# 4_324_039__3_2.net
KiCad netlist of a schematic drawn in Altium Designer
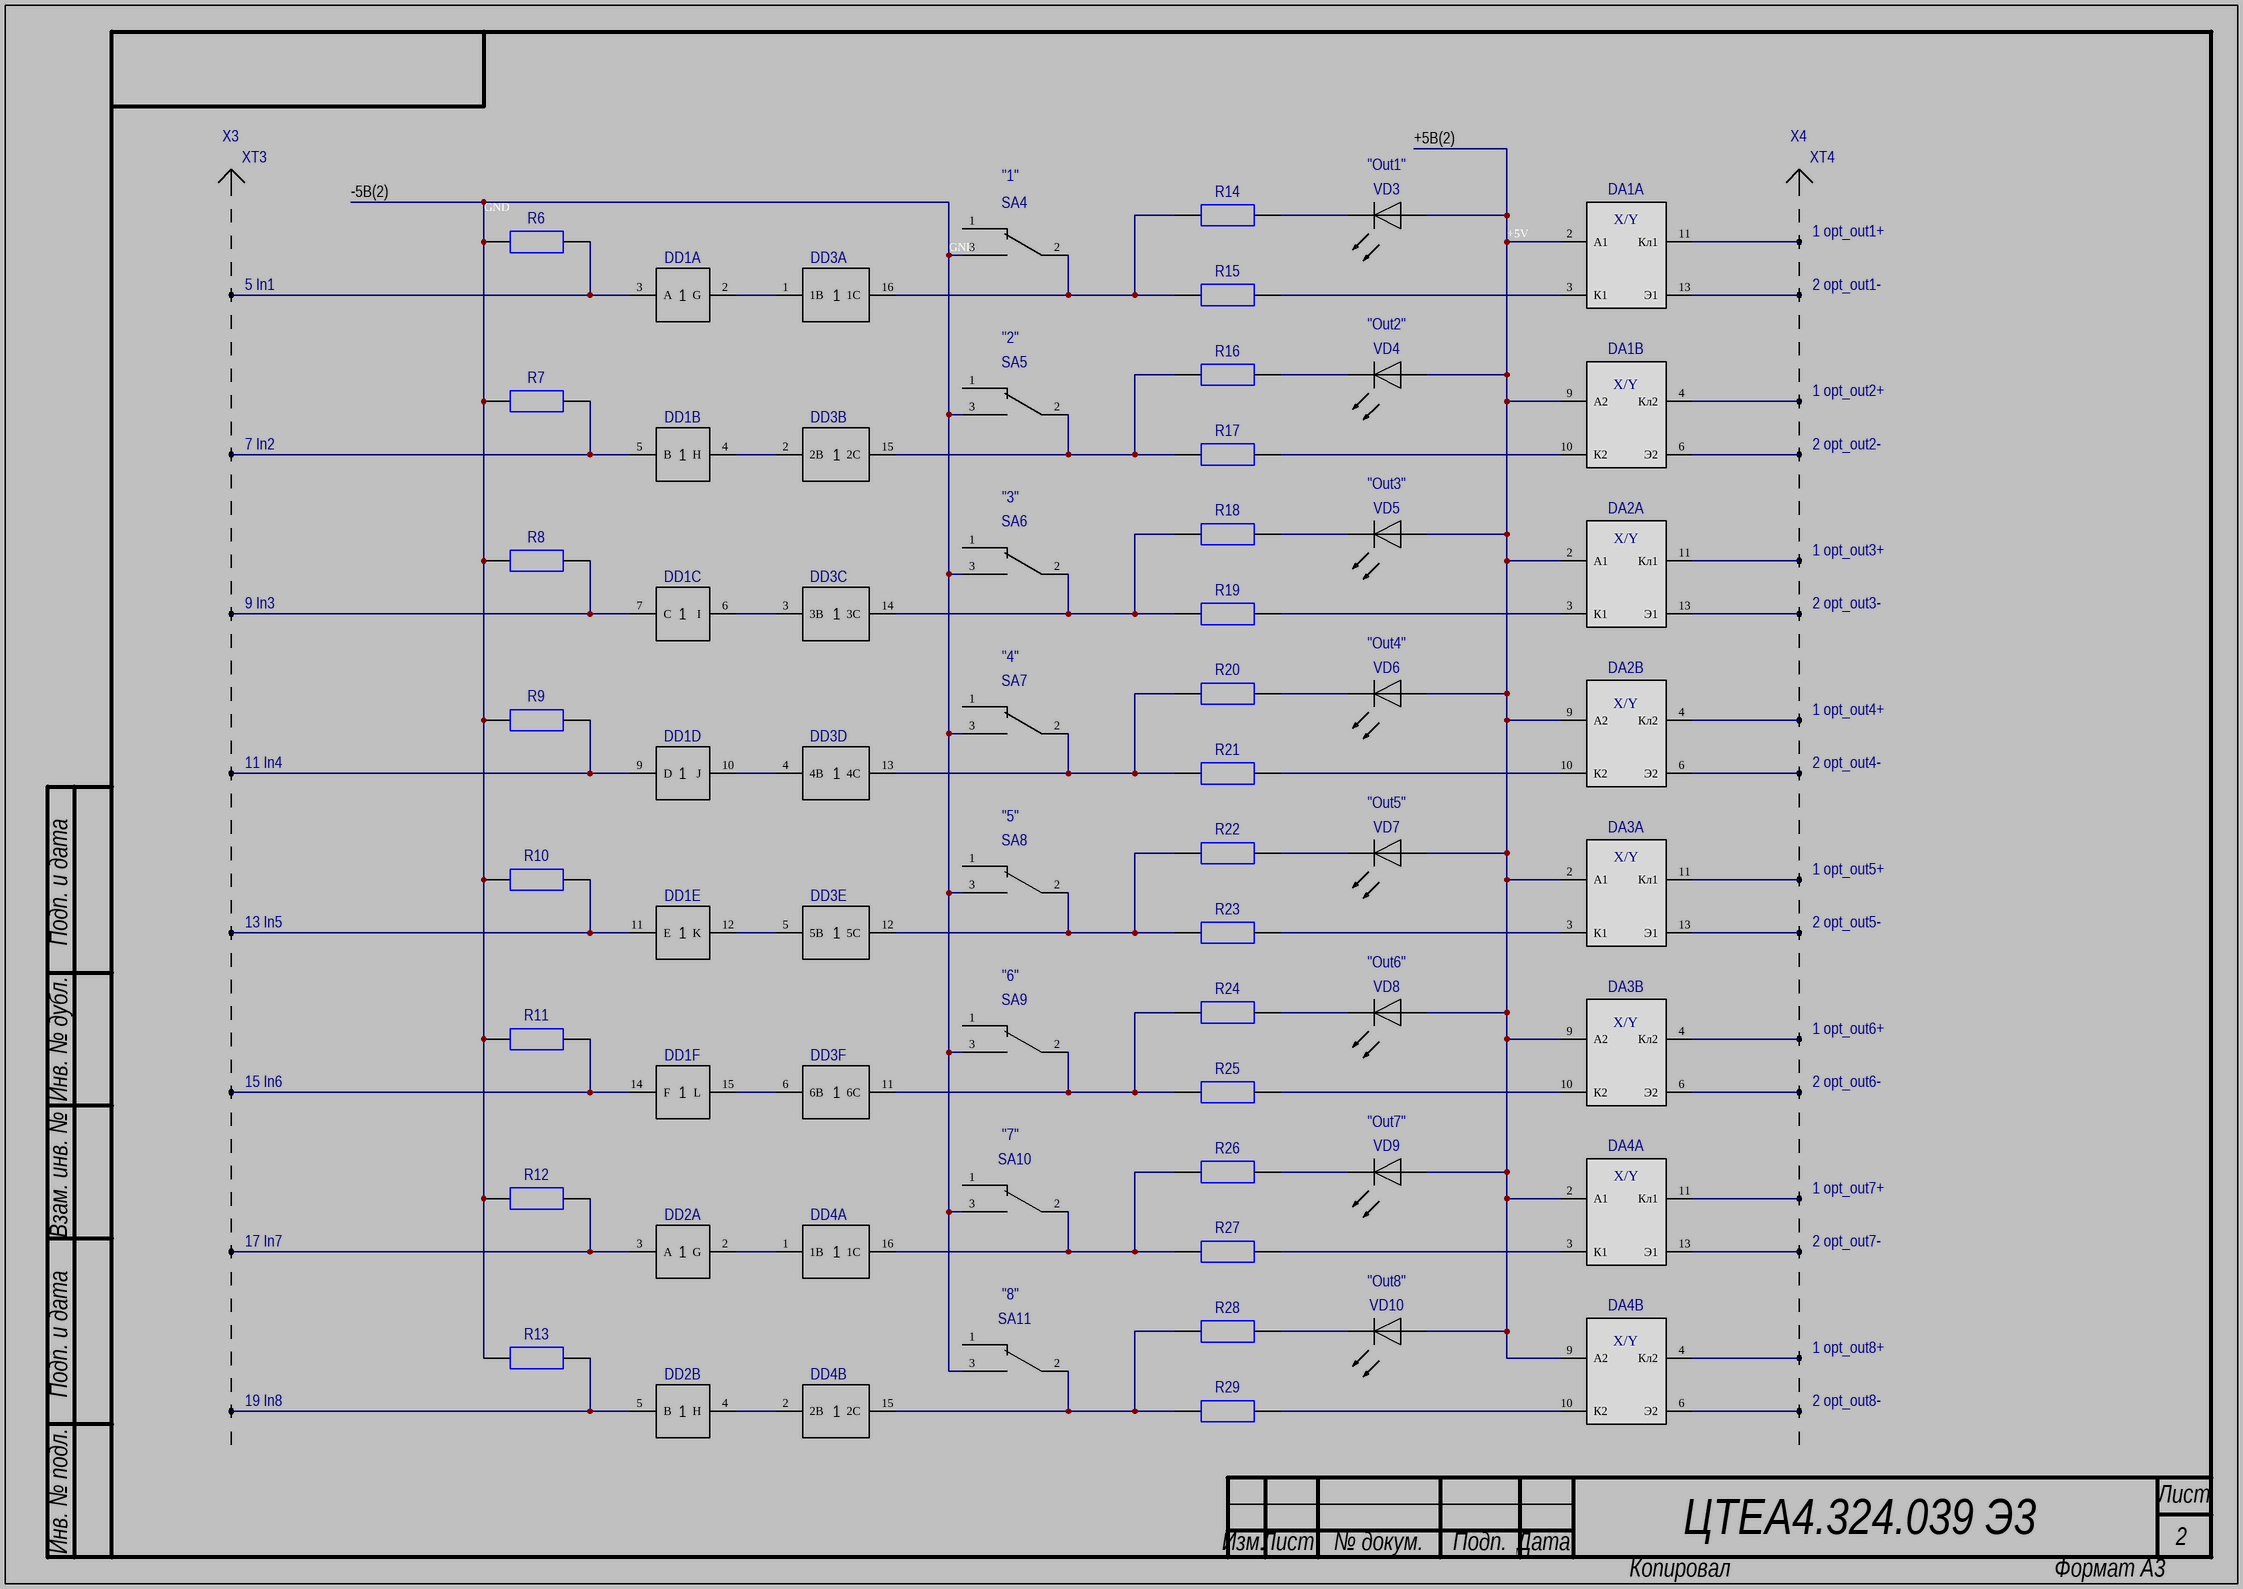
[diagram p0: ЦТЕА4.324.039_Э3_2.SchDoc]

(export (version "E")
  (design (tool "Eeschema 10.0.6"))
  (components
    (comp (ref "DA1")
      (value "249КП1С")
      (footprint "249KP1S_44_3208_125_12-3kl:249KP1S-44_3208_125_12")
      (libsource (lib "249KP1S_44_3208_125_12-3kl") (part "Microshema"))
    )
    (comp (ref "DA2")
      (value "249КП1С")
      (footprint "249KP1S_44_3208_125_12-3kl:249KP1S-44_3208_125_12")
      (libsource (lib "249KP1S_44_3208_125_12-3kl") (part "Microshema"))
    )
    (comp (ref "DA3")
      (value "249КП1С")
      (footprint "249KP1S_44_3208_125_12-3kl:249KP1S-44_3208_125_12")
      (libsource (lib "249KP1S_44_3208_125_12-3kl") (part "Microshema"))
    )
    (comp (ref "DA4")
      (value "249КП1С")
      (footprint "249KP1S_44_3208_125_12-3kl:249KP1S-44_3208_125_12")
      (libsource (lib "249KP1S_44_3208_125_12-3kl") (part "Microshema"))
    )
    (comp (ref "DD1")
      (value "Mikroshema")
      (footprint "CD4050BD")
      (description "CD4050BD")
      (libsource (lib "CD4050BD-3kl") (part "Mikroshema"))
    )
    (comp (ref "DD2")
      (value "Mikroshema")
      (footprint "CD4050BD")
      (description "CD4050BD")
      (libsource (lib "CD4050BD-3kl") (part "Mikroshema"))
    )
    (comp (ref "DD3")
      (value "Mikroshema")
      (footprint "UL2004AD")
      (description "ULN2004")
      (libsource (lib "ULN2004AD-3kl") (part "Mikroshema"))
    )
    (comp (ref "DD4")
      (value "Mikroshema")
      (footprint "UL2004AD")
      (description "ULN2004")
      (libsource (lib "ULN2004AD-3kl") (part "Mikroshema"))
    )
    (comp (ref "R6")
      (value "Res")
      (footprint "CR1206-JW-3301ELF")
      (libsource (lib "CR1206-JW-3301ELF-3kl") (part "Rezistor"))
    )
    (comp (ref "R7")
      (value "Res")
      (footprint "CR1206-JW-3301ELF")
      (libsource (lib "CR1206-JW-3301ELF-3kl") (part "Rezistor"))
    )
    (comp (ref "R8")
      (value "Res")
      (footprint "CR1206-JW-3301ELF")
      (libsource (lib "CR1206-JW-3301ELF-3kl") (part "Rezistor"))
    )
    (comp (ref "R9")
      (value "Res")
      (footprint "CR1206-JW-3301ELF")
      (libsource (lib "CR1206-JW-3301ELF-3kl") (part "Rezistor"))
    )
    (comp (ref "R10")
      (value "Res")
      (footprint "CR1206-JW-3301ELF")
      (libsource (lib "CR1206-JW-3301ELF-3kl") (part "Rezistor"))
    )
    (comp (ref "R11")
      (value "Res")
      (footprint "CR1206-JW-3301ELF")
      (libsource (lib "CR1206-JW-3301ELF-3kl") (part "Rezistor"))
    )
    (comp (ref "R12")
      (value "Res")
      (footprint "CR1206-JW-3301ELF")
      (libsource (lib "CR1206-JW-3301ELF-3kl") (part "Rezistor"))
    )
    (comp (ref "R13")
      (value "Res")
      (footprint "CR1206-JW-3301ELF")
      (libsource (lib "CR1206-JW-3301ELF-3kl") (part "Rezistor"))
    )
    (comp (ref "R14")
      (value "Res")
      (footprint "CR1206-JW-4700ELF")
      (libsource (lib "CR1206-JW-4700ELF-3kl") (part "Rezistor"))
    )
    (comp (ref "R15")
      (value "Res")
      (footprint "CR1206-JW-3300ELF")
      (libsource (lib "CR1206-JW-3300ELF-3kl") (part "Rezistor"))
    )
    (comp (ref "R16")
      (value "Res")
      (footprint "CR1206-JW-4700ELF")
      (libsource (lib "CR1206-JW-4700ELF-3kl") (part "Rezistor"))
    )
    (comp (ref "R17")
      (value "Res")
      (footprint "CR1206-JW-3300ELF")
      (libsource (lib "CR1206-JW-3300ELF-3kl") (part "Rezistor"))
    )
    (comp (ref "R18")
      (value "Res")
      (footprint "CR1206-JW-4700ELF")
      (libsource (lib "CR1206-JW-4700ELF-3kl") (part "Rezistor"))
    )
    (comp (ref "R19")
      (value "Res")
      (footprint "CR1206-JW-3300ELF")
      (libsource (lib "CR1206-JW-3300ELF-3kl") (part "Rezistor"))
    )
    (comp (ref "R20")
      (value "Res")
      (footprint "CR1206-JW-4700ELF")
      (libsource (lib "CR1206-JW-4700ELF-3kl") (part "Rezistor"))
    )
    (comp (ref "R21")
      (value "Res")
      (footprint "CR1206-JW-3300ELF")
      (libsource (lib "CR1206-JW-3300ELF-3kl") (part "Rezistor"))
    )
    (comp (ref "R22")
      (value "Res")
      (footprint "CR1206-JW-4700ELF")
      (libsource (lib "CR1206-JW-4700ELF-3kl") (part "Rezistor"))
    )
    (comp (ref "R23")
      (value "Res")
      (footprint "CR1206-JW-3300ELF")
      (libsource (lib "CR1206-JW-3300ELF-3kl") (part "Rezistor"))
    )
    (comp (ref "R24")
      (value "Res")
      (footprint "CR1206-JW-4700ELF")
      (libsource (lib "CR1206-JW-4700ELF-3kl") (part "Rezistor"))
    )
    (comp (ref "R25")
      (value "Res")
      (footprint "CR1206-JW-3300ELF")
      (libsource (lib "CR1206-JW-3300ELF-3kl") (part "Rezistor"))
    )
    (comp (ref "R26")
      (value "Res")
      (footprint "CR1206-JW-4700ELF")
      (libsource (lib "CR1206-JW-4700ELF-3kl") (part "Rezistor"))
    )
    (comp (ref "R27")
      (value "Res")
      (footprint "CR1206-JW-3300ELF")
      (libsource (lib "CR1206-JW-3300ELF-3kl") (part "Rezistor"))
    )
    (comp (ref "R28")
      (value "Res")
      (footprint "CR1206-JW-4700ELF")
      (libsource (lib "CR1206-JW-4700ELF-3kl") (part "Rezistor"))
    )
    (comp (ref "R29")
      (value "Res")
      (footprint "CR1206-JW-3300ELF")
      (libsource (lib "CR1206-JW-3300ELF-3kl") (part "Rezistor"))
    )
    (comp (ref "SA4")
      (value "\"1\"")
      (footprint "7101SYZQE-3kl:7107SYZQE")
      (libsource (lib "7101SYZQE-3kl") (part "Perekljuchatel"))
    )
    (comp (ref "SA5")
      (value "\"2\"")
      (footprint "7101SYZQE-3kl:7107SYZQE")
      (libsource (lib "7101SYZQE-3kl") (part "Perekljuchatel"))
    )
    (comp (ref "SA6")
      (value "\"3\"")
      (footprint "7101SYZQE-3kl:7107SYZQE")
      (libsource (lib "7101SYZQE-3kl") (part "Perekljuchatel"))
    )
    (comp (ref "SA7")
      (value "\"4\"")
      (footprint "7101SYZQE-3kl:7107SYZQE")
      (libsource (lib "7101SYZQE-3kl") (part "Perekljuchatel"))
    )
    (comp (ref "SA8")
      (value "\"5\"")
      (footprint "7101SYZQE-3kl:7107SYZQE")
      (libsource (lib "7101SYZQE-3kl") (part "Perekljuchatel"))
    )
    (comp (ref "SA9")
      (value "\"6\"")
      (footprint "7101SYZQE-3kl:7107SYZQE")
      (libsource (lib "7101SYZQE-3kl") (part "Perekljuchatel"))
    )
    (comp (ref "SA10")
      (value "\"7\"")
      (footprint "7101SYZQE-3kl:7107SYZQE")
      (libsource (lib "7101SYZQE-3kl") (part "Perekljuchatel"))
    )
    (comp (ref "SA11")
      (value "\"8\"")
      (footprint "7101SYZQE-3kl:7107SYZQE")
      (libsource (lib "7101SYZQE-3kl") (part "Perekljuchatel"))
    )
    (comp (ref "VD3")
      (value "\"Out1\"")
      (footprint "HLMP-D150")
      (libsource (lib "HLMP-D150-3kl") (part "Svetodiod"))
    )
    (comp (ref "VD4")
      (value "\"Out2\"")
      (footprint "HLMP-D150")
      (libsource (lib "HLMP-D150-3kl") (part "Svetodiod"))
    )
    (comp (ref "VD5")
      (value "\"Out3\"")
      (footprint "HLMP-D150")
      (libsource (lib "HLMP-D150-3kl") (part "Svetodiod"))
    )
    (comp (ref "VD6")
      (value "\"Out4\"")
      (footprint "HLMP-D150")
      (libsource (lib "HLMP-D150-3kl") (part "Svetodiod"))
    )
    (comp (ref "VD7")
      (value "\"Out5\"")
      (footprint "HLMP-D150")
      (libsource (lib "HLMP-D150-3kl") (part "Svetodiod"))
    )
    (comp (ref "VD8")
      (value "\"Out6\"")
      (footprint "HLMP-D150")
      (libsource (lib "HLMP-D150-3kl") (part "Svetodiod"))
    )
    (comp (ref "VD9")
      (value "\"Out7\"")
      (footprint "HLMP-D150")
      (libsource (lib "HLMP-D150-3kl") (part "Svetodiod"))
    )
    (comp (ref "VD10")
      (value "\"Out8\"")
      (footprint "HLMP-D150")
      (libsource (lib "HLMP-D150-3kl") (part "Svetodiod"))
    )
    (comp (ref "XT3")
      (value "17 In7")
      (footprint "PLD-40")
      (libsource (lib "PLD-40-3kl") (part "Razem shtyrevoj"))
    )
    (comp (ref "XT4")
      (value "1 opt_out1+")
      (footprint "PLD-18")
      (libsource (lib "PLD-18-3kl") (part "Razem shtyrevoj"))
    )
  )
  (nets
    (net (code "1") (name "/+5V") (class "Default")
      (node (ref "DA1") (pin "2") (pinfunction "А1_2") (pintype "passive"))
      (node (ref "DA1") (pin "9") (pinfunction "А2_9") (pintype "passive"))
      (node (ref "DA2") (pin "2") (pinfunction "А1_2") (pintype "passive"))
      (node (ref "DA2") (pin "9") (pinfunction "А2_9") (pintype "passive"))
      (node (ref "DA3") (pin "2") (pinfunction "А1_2") (pintype "passive"))
      (node (ref "DA3") (pin "9") (pinfunction "А2_9") (pintype "passive"))
      (node (ref "DA4") (pin "2") (pinfunction "А1_2") (pintype "passive"))
      (node (ref "DA4") (pin "9") (pinfunction "А2_9") (pintype "passive"))
      (node (ref "VD10") (pin "1") (pinfunction "A_1") (pintype "passive"))
      (node (ref "VD3") (pin "1") (pinfunction "A_1") (pintype "passive"))
      (node (ref "VD4") (pin "1") (pinfunction "A_1") (pintype "passive"))
      (node (ref "VD5") (pin "1") (pinfunction "A_1") (pintype "passive"))
      (node (ref "VD6") (pin "1") (pinfunction "A_1") (pintype "passive"))
      (node (ref "VD7") (pin "1") (pinfunction "A_1") (pintype "passive"))
      (node (ref "VD8") (pin "1") (pinfunction "A_1") (pintype "passive"))
      (node (ref "VD9") (pin "1") (pinfunction "A_1") (pintype "passive"))
    )
    (net (code "2") (name "/GND") (class "Default")
      (node (ref "R10") (pin "1") (pinfunction "1_1") (pintype "passive"))
      (node (ref "R11") (pin "1") (pinfunction "1_1") (pintype "passive"))
      (node (ref "R12") (pin "1") (pinfunction "1_1") (pintype "passive"))
      (node (ref "R13") (pin "1") (pinfunction "1_1") (pintype "passive"))
      (node (ref "R6") (pin "1") (pinfunction "1_1") (pintype "passive"))
      (node (ref "R7") (pin "1") (pinfunction "1_1") (pintype "passive"))
      (node (ref "R8") (pin "1") (pinfunction "1_1") (pintype "passive"))
      (node (ref "R9") (pin "1") (pinfunction "1_1") (pintype "passive"))
      (node (ref "SA10") (pin "3") (pinfunction "3_3") (pintype "passive"))
      (node (ref "SA11") (pin "3") (pinfunction "3_3") (pintype "passive"))
      (node (ref "SA4") (pin "3") (pinfunction "3_3") (pintype "passive"))
      (node (ref "SA5") (pin "3") (pinfunction "3_3") (pintype "passive"))
      (node (ref "SA6") (pin "3") (pinfunction "3_3") (pintype "passive"))
      (node (ref "SA7") (pin "3") (pinfunction "3_3") (pintype "passive"))
      (node (ref "SA8") (pin "3") (pinfunction "3_3") (pintype "passive"))
      (node (ref "SA9") (pin "3") (pinfunction "3_3") (pintype "passive"))
    )
    (net (code "3") (name "Net-(DA1A-К1)") (class "Default")
      (node (ref "DA1") (pin "3") (pinfunction "К1_3") (pintype "passive"))
      (node (ref "R15") (pin "2") (pinfunction "2_2") (pintype "passive"))
    )
    (net (code "4") (name "Net-(DA1A-Кл1)") (class "Default")
      (node (ref "DA1") (pin "11") (pinfunction "Кл1_11") (pintype "passive"))
      (node (ref "XT4") (pin "1") (pinfunction "1_1") (pintype "passive"))
    )
    (net (code "5") (name "Net-(DA1A-Э1)") (class "Default")
      (node (ref "DA1") (pin "13") (pinfunction "Э1_13") (pintype "passive"))
      (node (ref "XT4") (pin "2") (pinfunction "2_2") (pintype "passive"))
    )
    (net (code "6") (name "Net-(DA1B-К2)") (class "Default")
      (node (ref "DA1") (pin "10") (pinfunction "К2_10") (pintype "passive"))
      (node (ref "R17") (pin "2") (pinfunction "2_2") (pintype "passive"))
    )
    (net (code "7") (name "Net-(DA1B-Кл2)") (class "Default")
      (node (ref "DA1") (pin "4") (pinfunction "Кл2_4") (pintype "passive"))
      (node (ref "XT4") (pin "3") (pinfunction "3_3") (pintype "passive"))
    )
    (net (code "8") (name "Net-(DA1B-Э2)") (class "Default")
      (node (ref "DA1") (pin "6") (pinfunction "Э2_6") (pintype "passive"))
      (node (ref "XT4") (pin "4") (pinfunction "4_4") (pintype "passive"))
    )
    (net (code "9") (name "Net-(DA2A-К1)") (class "Default")
      (node (ref "DA2") (pin "3") (pinfunction "К1_3") (pintype "passive"))
      (node (ref "R19") (pin "2") (pinfunction "2_2") (pintype "passive"))
    )
    (net (code "10") (name "Net-(DA2A-Кл1)") (class "Default")
      (node (ref "DA2") (pin "11") (pinfunction "Кл1_11") (pintype "passive"))
      (node (ref "XT4") (pin "5") (pinfunction "5_5") (pintype "passive"))
    )
    (net (code "11") (name "Net-(DA2A-Э1)") (class "Default")
      (node (ref "DA2") (pin "13") (pinfunction "Э1_13") (pintype "passive"))
      (node (ref "XT4") (pin "6") (pinfunction "6_6") (pintype "passive"))
    )
    (net (code "12") (name "Net-(DA2B-К2)") (class "Default")
      (node (ref "DA2") (pin "10") (pinfunction "К2_10") (pintype "passive"))
      (node (ref "R21") (pin "2") (pinfunction "2_2") (pintype "passive"))
    )
    (net (code "13") (name "Net-(DA2B-Кл2)") (class "Default")
      (node (ref "DA2") (pin "4") (pinfunction "Кл2_4") (pintype "passive"))
      (node (ref "XT4") (pin "7") (pinfunction "7_7") (pintype "passive"))
    )
    (net (code "14") (name "Net-(DA2B-Э2)") (class "Default")
      (node (ref "DA2") (pin "6") (pinfunction "Э2_6") (pintype "passive"))
      (node (ref "XT4") (pin "8") (pinfunction "8_8") (pintype "passive"))
    )
    (net (code "15") (name "Net-(DA3A-К1)") (class "Default")
      (node (ref "DA3") (pin "3") (pinfunction "К1_3") (pintype "passive"))
      (node (ref "R23") (pin "2") (pinfunction "2_2") (pintype "passive"))
    )
    (net (code "16") (name "Net-(DA3A-Кл1)") (class "Default")
      (node (ref "DA3") (pin "11") (pinfunction "Кл1_11") (pintype "passive"))
      (node (ref "XT4") (pin "9") (pinfunction "9_9") (pintype "passive"))
    )
    (net (code "17") (name "Net-(DA3A-Э1)") (class "Default")
      (node (ref "DA3") (pin "13") (pinfunction "Э1_13") (pintype "passive"))
      (node (ref "XT4") (pin "10") (pinfunction "10_10") (pintype "passive"))
    )
    (net (code "18") (name "Net-(DA3B-К2)") (class "Default")
      (node (ref "DA3") (pin "10") (pinfunction "К2_10") (pintype "passive"))
      (node (ref "R25") (pin "2") (pinfunction "2_2") (pintype "passive"))
    )
    (net (code "19") (name "Net-(DA3B-Кл2)") (class "Default")
      (node (ref "DA3") (pin "4") (pinfunction "Кл2_4") (pintype "passive"))
      (node (ref "XT4") (pin "11") (pinfunction "11_11") (pintype "passive"))
    )
    (net (code "20") (name "Net-(DA3B-Э2)") (class "Default")
      (node (ref "DA3") (pin "6") (pinfunction "Э2_6") (pintype "passive"))
      (node (ref "XT4") (pin "12") (pinfunction "12_12") (pintype "passive"))
    )
    (net (code "21") (name "Net-(DA4A-К1)") (class "Default")
      (node (ref "DA4") (pin "3") (pinfunction "К1_3") (pintype "passive"))
      (node (ref "R27") (pin "2") (pinfunction "2_2") (pintype "passive"))
    )
    (net (code "22") (name "Net-(DA4A-Кл1)") (class "Default")
      (node (ref "DA4") (pin "11") (pinfunction "Кл1_11") (pintype "passive"))
      (node (ref "XT4") (pin "13") (pinfunction "13_13") (pintype "passive"))
    )
    (net (code "23") (name "Net-(DA4A-Э1)") (class "Default")
      (node (ref "DA4") (pin "13") (pinfunction "Э1_13") (pintype "passive"))
      (node (ref "XT4") (pin "14") (pinfunction "14_14") (pintype "passive"))
    )
    (net (code "24") (name "Net-(DA4B-К2)") (class "Default")
      (node (ref "DA4") (pin "10") (pinfunction "К2_10") (pintype "passive"))
      (node (ref "R29") (pin "2") (pinfunction "2_2") (pintype "passive"))
    )
    (net (code "25") (name "Net-(DA4B-Кл2)") (class "Default")
      (node (ref "DA4") (pin "4") (pinfunction "Кл2_4") (pintype "passive"))
      (node (ref "XT4") (pin "15") (pinfunction "15_15") (pintype "passive"))
    )
    (net (code "26") (name "Net-(DA4B-Э2)") (class "Default")
      (node (ref "DA4") (pin "6") (pinfunction "Э2_6") (pintype "passive"))
      (node (ref "XT4") (pin "16") (pinfunction "16_16") (pintype "passive"))
    )
    (net (code "27") (name "Net-(DD1A-A)") (class "Default")
      (node (ref "DD1") (pin "3") (pinfunction "A_3") (pintype "passive"))
      (node (ref "R6") (pin "2") (pinfunction "2_2") (pintype "passive"))
      (node (ref "XT3") (pin "5") (pinfunction "5_5") (pintype "passive"))
    )
    (net (code "28") (name "Net-(DD1A-G)") (class "Default")
      (node (ref "DD1") (pin "2") (pinfunction "G_2") (pintype "passive"))
      (node (ref "DD3") (pin "1") (pinfunction "1B_1") (pintype "passive"))
    )
    (net (code "29") (name "Net-(DD1B-B)") (class "Default")
      (node (ref "DD1") (pin "5") (pinfunction "B_5") (pintype "passive"))
      (node (ref "R7") (pin "2") (pinfunction "2_2") (pintype "passive"))
      (node (ref "XT3") (pin "7") (pinfunction "7_7") (pintype "passive"))
    )
    (net (code "30") (name "Net-(DD1B-H)") (class "Default")
      (node (ref "DD1") (pin "4") (pinfunction "H_4") (pintype "passive"))
      (node (ref "DD3") (pin "2") (pinfunction "2B_2") (pintype "passive"))
    )
    (net (code "31") (name "Net-(DD1C-C)") (class "Default")
      (node (ref "DD1") (pin "7") (pinfunction "C_7") (pintype "passive"))
      (node (ref "R8") (pin "2") (pinfunction "2_2") (pintype "passive"))
      (node (ref "XT3") (pin "9") (pinfunction "9_9") (pintype "passive"))
    )
    (net (code "32") (name "Net-(DD1C-I)") (class "Default")
      (node (ref "DD1") (pin "6") (pinfunction "I_6") (pintype "passive"))
      (node (ref "DD3") (pin "3") (pinfunction "3B_3") (pintype "passive"))
    )
    (net (code "33") (name "Net-(DD1D-D)") (class "Default")
      (node (ref "DD1") (pin "9") (pinfunction "D_9") (pintype "passive"))
      (node (ref "R9") (pin "2") (pinfunction "2_2") (pintype "passive"))
      (node (ref "XT3") (pin "11") (pinfunction "11_11") (pintype "passive"))
    )
    (net (code "34") (name "Net-(DD1D-J)") (class "Default")
      (node (ref "DD1") (pin "10") (pinfunction "J_10") (pintype "passive"))
      (node (ref "DD3") (pin "4") (pinfunction "4B_4") (pintype "passive"))
    )
    (net (code "35") (name "Net-(DD1E-E)") (class "Default")
      (node (ref "DD1") (pin "11") (pinfunction "E_11") (pintype "passive"))
      (node (ref "R10") (pin "2") (pinfunction "2_2") (pintype "passive"))
      (node (ref "XT3") (pin "13") (pinfunction "13_13") (pintype "passive"))
    )
    (net (code "36") (name "Net-(DD1E-K)") (class "Default")
      (node (ref "DD1") (pin "12") (pinfunction "K_12") (pintype "passive"))
      (node (ref "DD3") (pin "5") (pinfunction "5B_5") (pintype "passive"))
    )
    (net (code "37") (name "Net-(DD1F-F)") (class "Default")
      (node (ref "DD1") (pin "14") (pinfunction "F_14") (pintype "passive"))
      (node (ref "R11") (pin "2") (pinfunction "2_2") (pintype "passive"))
      (node (ref "XT3") (pin "15") (pinfunction "15_15") (pintype "passive"))
    )
    (net (code "38") (name "Net-(DD1F-L)") (class "Default")
      (node (ref "DD1") (pin "15") (pinfunction "L_15") (pintype "passive"))
      (node (ref "DD3") (pin "6") (pinfunction "6B_6") (pintype "passive"))
    )
    (net (code "39") (name "Net-(DD2A-A)") (class "Default")
      (node (ref "DD2") (pin "3") (pinfunction "A_3") (pintype "passive"))
      (node (ref "R12") (pin "2") (pinfunction "2_2") (pintype "passive"))
      (node (ref "XT3") (pin "17") (pinfunction "17_17") (pintype "passive"))
    )
    (net (code "40") (name "Net-(DD2A-G)") (class "Default")
      (node (ref "DD2") (pin "2") (pinfunction "G_2") (pintype "passive"))
      (node (ref "DD4") (pin "1") (pinfunction "1B_1") (pintype "passive"))
    )
    (net (code "41") (name "Net-(DD2B-B)") (class "Default")
      (node (ref "DD2") (pin "5") (pinfunction "B_5") (pintype "passive"))
      (node (ref "R13") (pin "2") (pinfunction "2_2") (pintype "passive"))
      (node (ref "XT3") (pin "19") (pinfunction "19_19") (pintype "passive"))
    )
    (net (code "42") (name "Net-(DD2B-H)") (class "Default")
      (node (ref "DD2") (pin "4") (pinfunction "H_4") (pintype "passive"))
      (node (ref "DD4") (pin "2") (pinfunction "2B_2") (pintype "passive"))
    )
    (net (code "43") (name "Net-(DD3A-1C)") (class "Default")
      (node (ref "DD3") (pin "16") (pinfunction "1C_16") (pintype "passive"))
      (node (ref "R14") (pin "1") (pinfunction "1_1") (pintype "passive"))
      (node (ref "R15") (pin "1") (pinfunction "1_1") (pintype "passive"))
      (node (ref "SA4") (pin "2") (pinfunction "2_2") (pintype "passive"))
    )
    (net (code "44") (name "Net-(DD3B-2C)") (class "Default")
      (node (ref "DD3") (pin "15") (pinfunction "2C_15") (pintype "passive"))
      (node (ref "R16") (pin "1") (pinfunction "1_1") (pintype "passive"))
      (node (ref "R17") (pin "1") (pinfunction "1_1") (pintype "passive"))
      (node (ref "SA5") (pin "2") (pinfunction "2_2") (pintype "passive"))
    )
    (net (code "45") (name "Net-(DD3C-3C)") (class "Default")
      (node (ref "DD3") (pin "14") (pinfunction "3C_14") (pintype "passive"))
      (node (ref "R18") (pin "1") (pinfunction "1_1") (pintype "passive"))
      (node (ref "R19") (pin "1") (pinfunction "1_1") (pintype "passive"))
      (node (ref "SA6") (pin "2") (pinfunction "2_2") (pintype "passive"))
    )
    (net (code "46") (name "Net-(DD3D-4C)") (class "Default")
      (node (ref "DD3") (pin "13") (pinfunction "4C_13") (pintype "passive"))
      (node (ref "R20") (pin "1") (pinfunction "1_1") (pintype "passive"))
      (node (ref "R21") (pin "1") (pinfunction "1_1") (pintype "passive"))
      (node (ref "SA7") (pin "2") (pinfunction "2_2") (pintype "passive"))
    )
    (net (code "47") (name "Net-(DD3E-5C)") (class "Default")
      (node (ref "DD3") (pin "12") (pinfunction "5C_12") (pintype "passive"))
      (node (ref "R22") (pin "1") (pinfunction "1_1") (pintype "passive"))
      (node (ref "R23") (pin "1") (pinfunction "1_1") (pintype "passive"))
      (node (ref "SA8") (pin "2") (pinfunction "2_2") (pintype "passive"))
    )
    (net (code "48") (name "Net-(DD3F-6C)") (class "Default")
      (node (ref "DD3") (pin "11") (pinfunction "6C_11") (pintype "passive"))
      (node (ref "R24") (pin "1") (pinfunction "1_1") (pintype "passive"))
      (node (ref "R25") (pin "1") (pinfunction "1_1") (pintype "passive"))
      (node (ref "SA9") (pin "2") (pinfunction "2_2") (pintype "passive"))
    )
    (net (code "49") (name "Net-(DD4A-1C)") (class "Default")
      (node (ref "DD4") (pin "16") (pinfunction "1C_16") (pintype "passive"))
      (node (ref "R26") (pin "1") (pinfunction "1_1") (pintype "passive"))
      (node (ref "R27") (pin "1") (pinfunction "1_1") (pintype "passive"))
      (node (ref "SA10") (pin "2") (pinfunction "2_2") (pintype "passive"))
    )
    (net (code "50") (name "Net-(DD4B-2C)") (class "Default")
      (node (ref "DD4") (pin "15") (pinfunction "2C_15") (pintype "passive"))
      (node (ref "R28") (pin "1") (pinfunction "1_1") (pintype "passive"))
      (node (ref "R29") (pin "1") (pinfunction "1_1") (pintype "passive"))
      (node (ref "SA11") (pin "2") (pinfunction "2_2") (pintype "passive"))
    )
    (net (code "51") (name "Net-(VD3-C)") (class "Default")
      (node (ref "R14") (pin "2") (pinfunction "2_2") (pintype "passive"))
      (node (ref "VD3") (pin "2") (pinfunction "C_2") (pintype "passive"))
    )
    (net (code "52") (name "Net-(VD4-C)") (class "Default")
      (node (ref "R16") (pin "2") (pinfunction "2_2") (pintype "passive"))
      (node (ref "VD4") (pin "2") (pinfunction "C_2") (pintype "passive"))
    )
    (net (code "53") (name "Net-(VD5-C)") (class "Default")
      (node (ref "R18") (pin "2") (pinfunction "2_2") (pintype "passive"))
      (node (ref "VD5") (pin "2") (pinfunction "C_2") (pintype "passive"))
    )
    (net (code "54") (name "Net-(VD6-C)") (class "Default")
      (node (ref "R20") (pin "2") (pinfunction "2_2") (pintype "passive"))
      (node (ref "VD6") (pin "2") (pinfunction "C_2") (pintype "passive"))
    )
    (net (code "55") (name "Net-(VD7-C)") (class "Default")
      (node (ref "R22") (pin "2") (pinfunction "2_2") (pintype "passive"))
      (node (ref "VD7") (pin "2") (pinfunction "C_2") (pintype "passive"))
    )
    (net (code "56") (name "Net-(VD8-C)") (class "Default")
      (node (ref "R24") (pin "2") (pinfunction "2_2") (pintype "passive"))
      (node (ref "VD8") (pin "2") (pinfunction "C_2") (pintype "passive"))
    )
    (net (code "57") (name "Net-(VD9-C)") (class "Default")
      (node (ref "R26") (pin "2") (pinfunction "2_2") (pintype "passive"))
      (node (ref "VD9") (pin "2") (pinfunction "C_2") (pintype "passive"))
    )
    (net (code "58") (name "Net-(VD10-C)") (class "Default")
      (node (ref "R28") (pin "2") (pinfunction "2_2") (pintype "passive"))
      (node (ref "VD10") (pin "2") (pinfunction "C_2") (pintype "passive"))
    )
    (net (code "59") (name "unconnected-(SA4-Pad1)") (class "Default")
      (node (ref "SA4") (pin "1") (pinfunction "1_1") (pintype "passive"))
    )
    (net (code "60") (name "unconnected-(SA5-Pad1)") (class "Default")
      (node (ref "SA5") (pin "1") (pinfunction "1_1") (pintype "passive"))
    )
    (net (code "61") (name "unconnected-(SA6-Pad1)") (class "Default")
      (node (ref "SA6") (pin "1") (pinfunction "1_1") (pintype "passive"))
    )
    (net (code "62") (name "unconnected-(SA7-Pad1)") (class "Default")
      (node (ref "SA7") (pin "1") (pinfunction "1_1") (pintype "passive"))
    )
    (net (code "63") (name "unconnected-(SA8-Pad1)") (class "Default")
      (node (ref "SA8") (pin "1") (pinfunction "1_1") (pintype "passive"))
    )
    (net (code "64") (name "unconnected-(SA9-Pad1)") (class "Default")
      (node (ref "SA9") (pin "1") (pinfunction "1_1") (pintype "passive"))
    )
    (net (code "65") (name "unconnected-(SA10-Pad1)") (class "Default")
      (node (ref "SA10") (pin "1") (pinfunction "1_1") (pintype "passive"))
    )
    (net (code "66") (name "unconnected-(SA11-Pad1)") (class "Default")
      (node (ref "SA11") (pin "1") (pinfunction "1_1") (pintype "passive"))
    )
  )
)
